# CH32V467VET-R0.net
KiCad netlist of a schematic drawn in Altium Designer
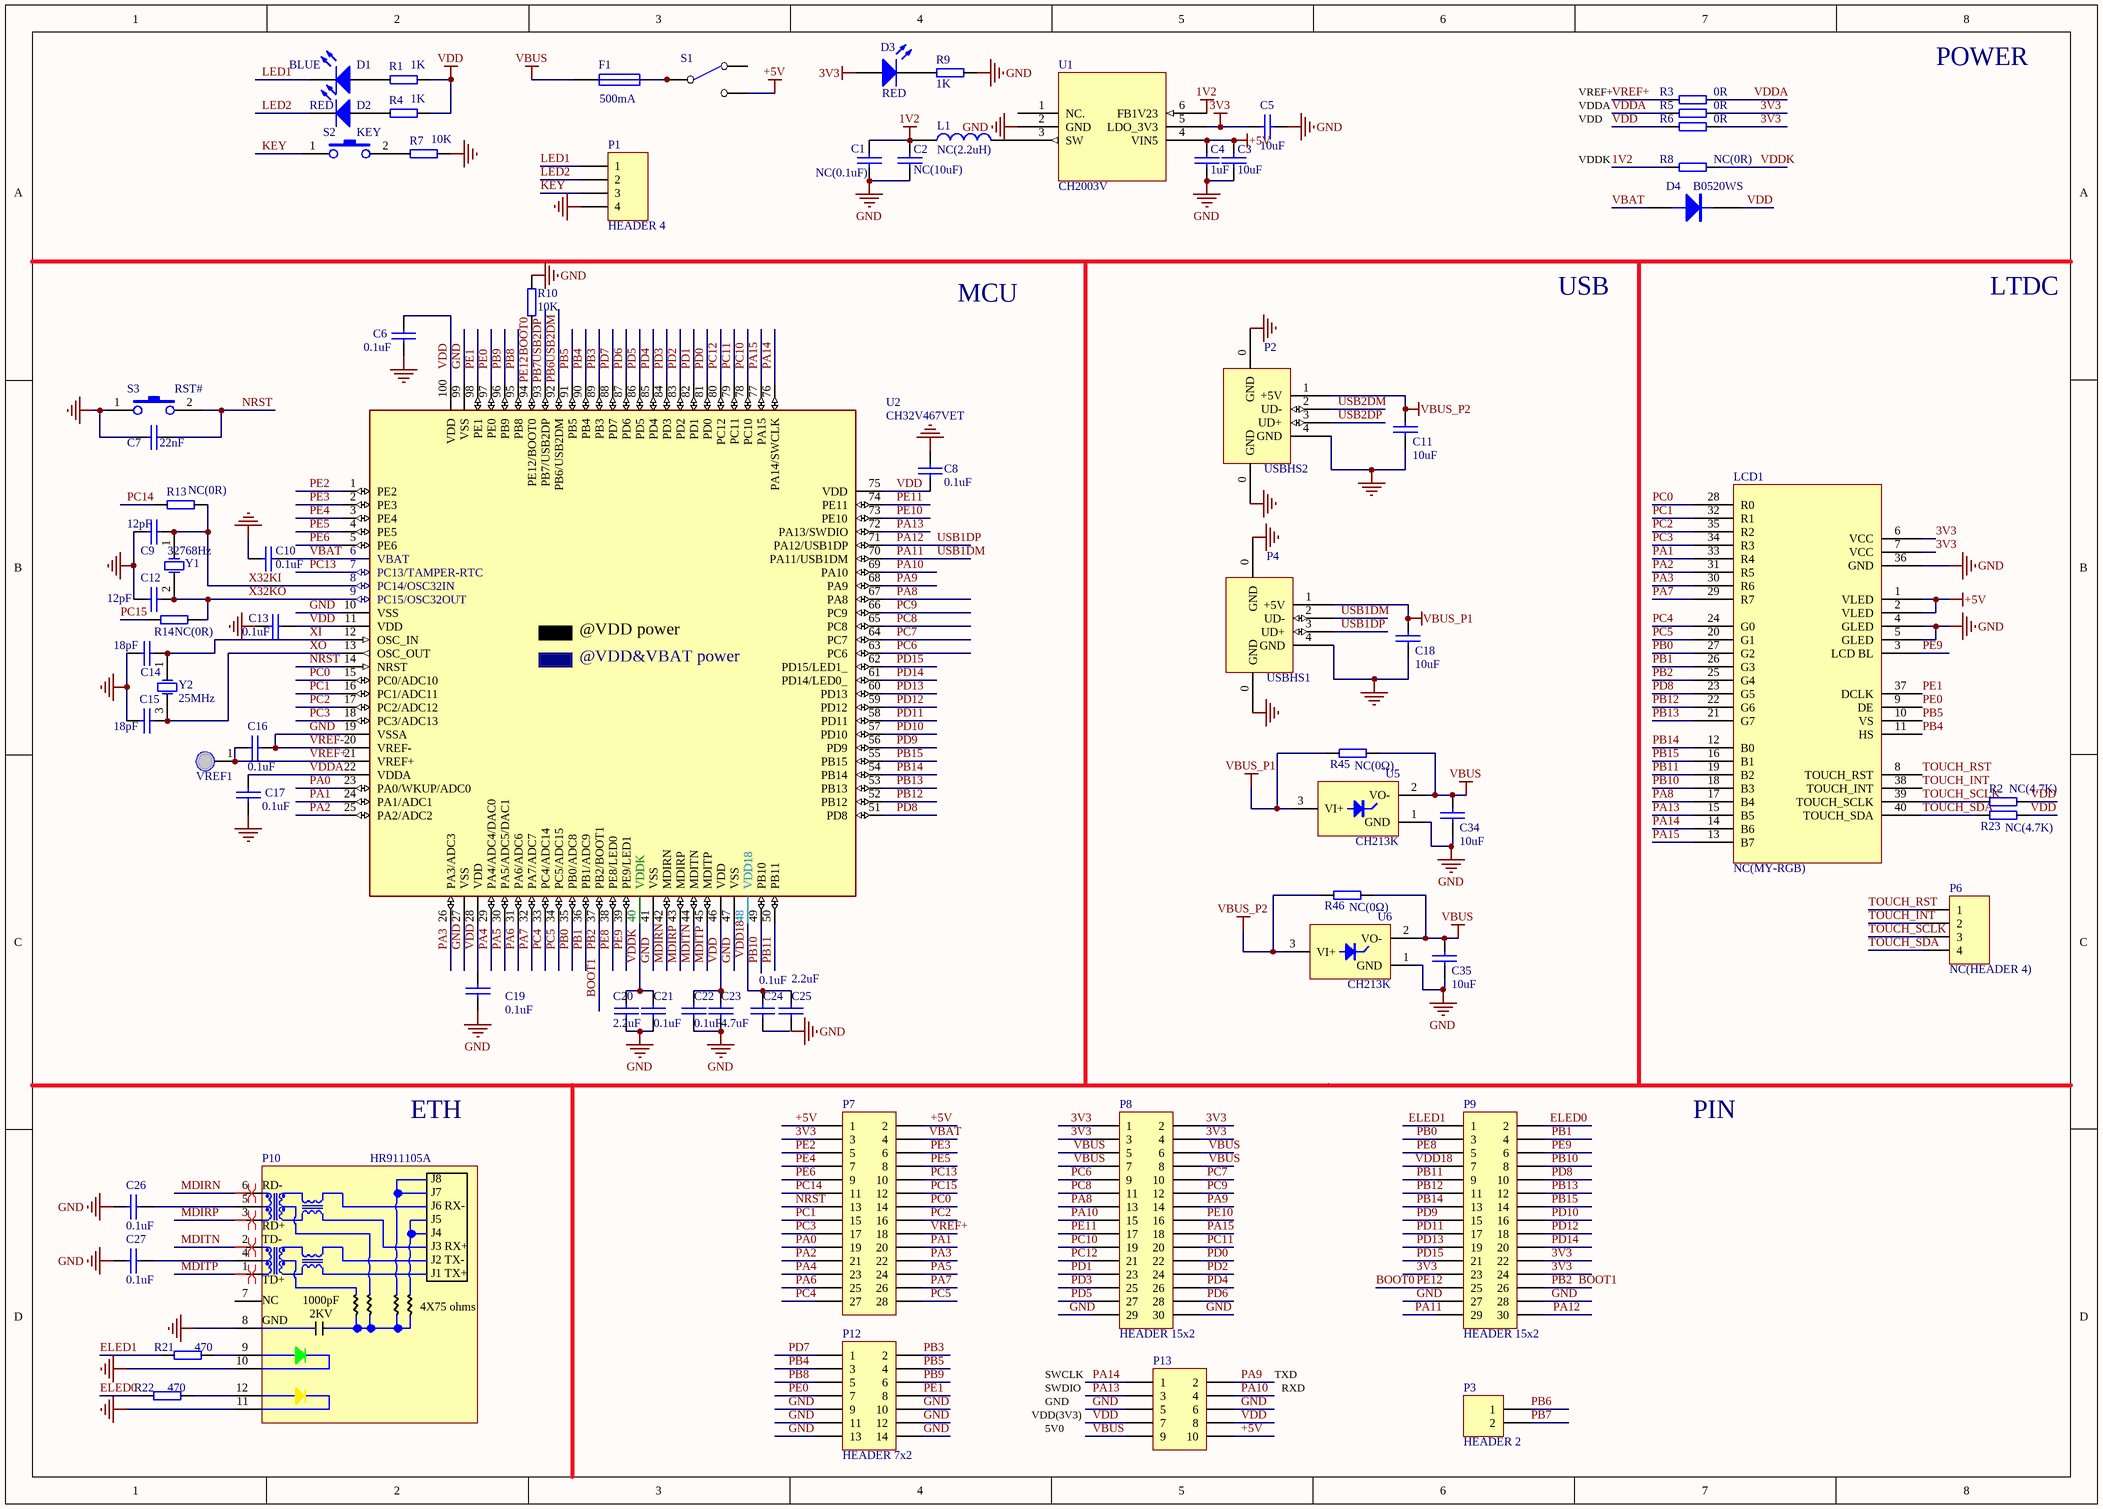
[diagram p0: CH32V467VET-R0.SchDoc]

(export (version "E")
  (design (tool "Eeschema 10.0.6"))
  (components
    (comp (ref "C1")
      (value "NC(0.1uF)")
      (footprint "0402_C")
      (description "Capacitor")
      (libsource (lib "") (part "CAP_2"))
    )
    (comp (ref "C2")
      (value "NC(10uF)")
      (footprint "0603_C")
      (description "Capacitor")
      (libsource (lib "*") (part "CAP"))
    )
    (comp (ref "C3")
      (value "10uF")
      (footprint "0603_C")
      (description "Capacitor")
      (libsource (lib "*") (part "CAP"))
    )
    (comp (ref "C4")
      (value "1uF")
      (footprint "0402_C")
      (description "Capacitor")
      (libsource (lib "") (part "CAP_2"))
    )
    (comp (ref "C5")
      (value "10uF")
      (footprint "0603_C")
      (description "Capacitor")
      (libsource (lib "*") (part "CAP"))
    )
    (comp (ref "C6")
      (value "0.1uF")
      (footprint "0402_C")
      (description "Capacitor")
      (libsource (lib "*") (part "CAP"))
    )
    (comp (ref "C7")
      (value "22nF")
      (footprint "0402_C")
      (description "Capacitor")
      (libsource (lib "") (part "CAP_1"))
    )
    (comp (ref "C8")
      (value "0.1uF")
      (footprint "0402_C")
      (description "Capacitor")
      (libsource (lib "*") (part "CAP"))
    )
    (comp (ref "C9")
      (value "12pF")
      (footprint "0402_C")
      (description "Capacitor")
      (libsource (lib "*") (part "CAP"))
    )
    (comp (ref "C10")
      (value "0.1uF")
      (footprint "0402_C")
      (description "Capacitor")
      (libsource (lib "*") (part "CAP"))
    )
    (comp (ref "C11")
      (value "10uF")
      (footprint "0603_C")
      (description "Capacitor")
      (libsource (lib "") (part "CAP_1"))
    )
    (comp (ref "C12")
      (value "12pF")
      (footprint "0402_C")
      (description "Capacitor")
      (libsource (lib "*") (part "CAP"))
    )
    (comp (ref "C13")
      (value "0.1uF")
      (footprint "0402_C")
      (description "Capacitor")
      (libsource (lib "*") (part "CAP"))
    )
    (comp (ref "C14")
      (value "18pF")
      (footprint "0402_C")
      (description "Capacitor")
      (libsource (lib "*") (part "CAP"))
    )
    (comp (ref "C15")
      (value "18pF")
      (footprint "0402_C")
      (description "Capacitor")
      (libsource (lib "*") (part "CAP"))
    )
    (comp (ref "C16")
      (value "0.1uF")
      (footprint "0402_C")
      (description "Capacitor")
      (libsource (lib "*") (part "CAP"))
    )
    (comp (ref "C17")
      (value "0.1uF")
      (footprint "0402_C")
      (description "Capacitor")
      (libsource (lib "*") (part "CAP"))
    )
    (comp (ref "C18")
      (value "10uF")
      (footprint "0603_C")
      (description "Capacitor")
      (libsource (lib "") (part "CAP_1"))
    )
    (comp (ref "C19")
      (value "0.1uF")
      (footprint "0402_C")
      (description "Capacitor")
      (libsource (lib "*") (part "CAP"))
    )
    (comp (ref "C20")
      (value "2.2uF")
      (footprint "0402_C")
      (description "Capacitor")
      (libsource (lib "*") (part "CAP"))
    )
    (comp (ref "C21")
      (value "0.1uF")
      (footprint "0402_C")
      (description "Capacitor")
      (libsource (lib "*") (part "CAP"))
    )
    (comp (ref "C22")
      (value "0.1uF")
      (footprint "0402_C")
      (description "Capacitor")
      (libsource (lib "*") (part "CAP"))
    )
    (comp (ref "C23")
      (value "4.7uF")
      (footprint "0402_C")
      (description "Capacitor")
      (libsource (lib "*") (part "CAP"))
    )
    (comp (ref "C24")
      (value "0.1uF")
      (footprint "0402_C")
      (description "Capacitor")
      (libsource (lib "*") (part "CAP"))
    )
    (comp (ref "C25")
      (value "2.2uF")
      (footprint "0402_C")
      (description "Capacitor")
      (libsource (lib "*") (part "CAP"))
    )
    (comp (ref "C26")
      (value "0.1uF")
      (footprint "0402_C")
      (description "Capacitor")
      (libsource (lib "wch_sch_others") (part "CAP"))
    )
    (comp (ref "C27")
      (value "0.1uF")
      (footprint "0402_C")
      (description "Capacitor")
      (libsource (lib "wch_sch_others") (part "CAP"))
    )
    (comp (ref "C34")
      (value "10uF")
      (footprint "0603_C")
      (description "Capacitor")
      (libsource (lib "") (part "CAP_1"))
    )
    (comp (ref "C35")
      (value "10uF")
      (footprint "0603_C")
      (description "Capacitor")
      (libsource (lib "") (part "CAP_1"))
    )
    (comp (ref "D1")
      (value "BLUE")
      (footprint "0603+")
      (description "Typical INFRARED GaAs LED")
      (fields (field (name "PUBLISHER") "Altium Limited"))
      (libsource (lib "*") (part "LED0"))
    )
    (comp (ref "D2")
      (value "RED")
      (footprint "0603+")
      (description "Typical INFRARED GaAs LED")
      (fields (field (name "PUBLISHER") "Altium Limited"))
      (libsource (lib "*") (part "LED0"))
    )
    (comp (ref "D3")
      (value "RED")
      (footprint "0603+")
      (description "Typical INFRARED GaAs LED")
      (fields (field (name "PUBLISHER") "Altium Limited"))
      (libsource (lib "*") (part "LED0"))
    )
    (comp (ref "D4")
      (value "B0520WS")
      (footprint "SOD-323")
      (description "Diode")
      (libsource (lib "*") (part "DIODE"))
    )
    (comp (ref "F1")
      (value "500mA")
      (footprint "0603")
      (description "Fuse")
      (libsource (lib "wch_sch_others") (part "FUSE1"))
    )
    (comp (ref "L1") (value "NC(2.2uH)") (footprint "CD32") (libsource (lib "*") (part "INDUCTOR")))
    (comp (ref "LCD1")
      (value "NC(MY-RGB)")
      (footprint "FPC40P-0.5-FK750M3")
      (libsource (lib "MY-显示") (part "MY-RGB"))
    )
    (comp (ref "P1")
      (value "HEADER 4")
      (footprint "SIP4-2.54mm")
      (description "Header, 4-Pin")
      (libsource (lib "wch_sch_others") (part "HEADER 4"))
    )
    (comp (ref "P2")
      (value "USBHS2")
      (footprint "USBAF")
      (description "USB Port")
      (libsource (lib "*") (part "USB"))
    )
    (comp (ref "P3")
      (value "HEADER 2")
      (footprint "MYPCB:SIP2-2.54mm")
      (description "Header, 2-Pin")
      (libsource (lib "wch_sch_others") (part "HEADER 2"))
    )
    (comp (ref "P4")
      (value "USBHS1")
      (footprint "USBAF")
      (description "USB Port")
      (libsource (lib "*") (part "USB"))
    )
    (comp (ref "P6")
      (value "NC(HEADER 4)")
      (footprint "SIP4-2.54mm")
      (description "Header, 4-Pin")
      (libsource (lib "wch_sch_others") (part "HEADER 4"))
    )
    (comp (ref "P7")
      (value "HEADER 14x2")
      (footprint "MYPCB:IDC28-2.54MM")
      (description "Header, 14-Pin, Dual row")
      (libsource (lib "wch_sch_others") (part "HEADER 14x2"))
    )
    (comp (ref "P8")
      (value "HEADER 15x2")
      (footprint "MYPCB:IDC30-2.54MM")
      (description "Header, 15-Pin, Dual row")
      (libsource (lib "wch_sch_others") (part "HEADER 15x2"))
    )
    (comp (ref "P9")
      (value "HEADER 15x2")
      (footprint "MYPCB:IDC30-2.54MM")
      (description "Header, 15-Pin, Dual row")
      (libsource (lib "wch_sch_others") (part "HEADER 15x2"))
    )
    (comp (ref "P10") (value "HR911105A") (footprint "HR911105A") (libsource (lib "*") (part "HR911105A")))
    (comp (ref "P12")
      (value "HEADER 7x2")
      (footprint "MYPCB:IDC14-2.54mm")
      (description "Header, 7-Pin, Dual row")
      (libsource (lib "wch_sch_others") (part "HEADER 7x2"))
    )
    (comp (ref "P13")
      (value "LINK")
      (footprint "IDC10-2.54mm")
      (description "Header, 5-Pin, Dual row, Right Angle")
      (fields (field (name "PUBLISHER") "Altium Limited"))
      (libsource (lib "Miscellaneous Connectors") (part "Header 5X2H"))
    )
    (comp (ref "R1") (value "1K") (footprint "0402") (libsource (lib "wch_sch_others") (part "RES")))
    (comp (ref "R2") (value "NC(4.7K)") (footprint "0402") (libsource (lib "wch_sch_others") (part "RES")))
    (comp (ref "R3") (value "0R") (footprint "0402") (libsource (lib "*") (part "R")))
    (comp (ref "R4") (value "1K") (footprint "0402") (libsource (lib "wch_sch_others") (part "RES")))
    (comp (ref "R5") (value "0R") (footprint "0402") (libsource (lib "*") (part "R")))
    (comp (ref "R6") (value "0R") (footprint "0402") (libsource (lib "*") (part "R")))
    (comp (ref "R7") (value "10K") (footprint "0402") (libsource (lib "wch_sch_others") (part "RES")))
    (comp (ref "R8") (value "NC(0R)") (footprint "0402") (libsource (lib "*") (part "R")))
    (comp (ref "R9") (value "1K") (footprint "0402") (libsource (lib "wch_sch_others") (part "RES")))
    (comp (ref "R10") (value "10K") (footprint "0402") (libsource (lib "wch_sch_others") (part "RES")))
    (comp (ref "R13") (value "NC(0R)") (footprint "0402") (libsource (lib "wch_sch_others") (part "RES")))
    (comp (ref "R14") (value "NC(0R)") (footprint "0402") (libsource (lib "wch_sch_others") (part "RES")))
    (comp (ref "R21") (value "470") (footprint "0402") (libsource (lib "wch_sch_others") (part "RES")))
    (comp (ref "R22") (value "470") (footprint "0402") (libsource (lib "wch_sch_others") (part "RES")))
    (comp (ref "R23") (value "NC(4.7K)") (footprint "0402") (libsource (lib "wch_sch_others") (part "RES")))
    (comp (ref "R45") (value "NC(0Ω)") (footprint "0402") (libsource (lib "wch_sch_others") (part "RES")))
    (comp (ref "R46") (value "NC(0Ω)") (footprint "0402") (libsource (lib "wch_sch_others") (part "RES")))
    (comp (ref "S1") (value "SW SPDT") (footprint "SW1") (libsource (lib "*") (part "SW SPDT")))
    (comp (ref "S2")
      (value "KEY")
      (footprint "SMD_6.1x3.65x2.5mm-KEY")
      (libsource (lib "wch_sch_others") (part "KEY1"))
    )
    (comp (ref "S3")
      (value "RST#")
      (footprint "SMD_6.1x3.65x2.5mm-KEY")
      (libsource (lib "wch_sch_others") (part "KEY1"))
    )
    (comp (ref "U1")
      (value "CH2003V")
      (footprint "SOT-23-6")
      (description "Step-Down DC-DC Converter, 5V input, 1.23V * 800mA output, with LDO 3.3V * 200mA")
      (libsource (lib "CHXXX") (part "CH2003V"))
    )
    (comp (ref "U2")
      (value "CH32V467VET")
      (footprint "LQFP100")
      (description "RISC-V FPU HD-MCU, 175MHz, USB_480M, 100M Ethernet & Phy, CAN, DVP, ADC, DAC, SRAM")
      (libsource (lib "CHXXX") (part "CH32V467VET"))
    )
    (comp (ref "U5")
      (value "CH213K")
      (footprint "SOT-23-3")
      (description "Ideal Diode 5V*1A")
      (libsource (lib "*") (part "CH213K"))
    )
    (comp (ref "U6")
      (value "CH213K")
      (footprint "SOT-23-3")
      (description "Ideal Diode 5V*1A")
      (libsource (lib "*") (part "CH213K"))
    )
    (comp (ref "VREF1")
      (value "PAD")
      (footprint "TESTPOINT1")
      (description "焊盘")
      (libsource (lib "wch_sch_others") (part "PAD"))
    )
    (comp (ref "Y1")
      (value "32768Hz")
      (footprint "FC-135")
      (description "Crystal Oscillator")
      (fields (field (name "PUBLISHER") "Altium Limited"))
      (libsource (lib "*") (part "XTAL"))
    )
    (comp (ref "Y2")
      (value "25MHz")
      (footprint "XT3225")
      (description "Crystal Oscillator")
      (fields (field (name "PUBLISHER") "Altium Limited"))
      (libsource (lib "") (part "XTAL_1"))
    )
  )
  (nets
    (net (code "1") (name "+5V") (class "Default")
      (node (ref "C3") (pin "2") (pinfunction "2_2") (pintype "passive"))
      (node (ref "C4") (pin "2") (pinfunction "2_2") (pintype "passive"))
      (node (ref "LCD1") (pin "1") (pinfunction "VLED_1") (pintype "passive"))
      (node (ref "LCD1") (pin "2") (pinfunction "VLED_2") (pintype "passive"))
      (node (ref "P13") (pin "10") (pinfunction "10_10") (pintype "passive"))
      (node (ref "P7") (pin "1") (pinfunction "1_1") (pintype "passive"))
      (node (ref "P7") (pin "2") (pinfunction "2_2") (pintype "passive"))
      (node (ref "S1") (pin "2") (pinfunction "NC_2") (pintype "passive"))
      (node (ref "U1") (pin "4") (pinfunction "VIN5_4") (pintype "power_in"))
    )
    (net (code "3") (name "/BOOT0") (class "Default")
      (node (ref "P9") (pin "25") (pinfunction "25_25") (pintype "passive"))
      (node (ref "R10") (pin "2") (pintype "passive"))
      (node (ref "U2") (pin "94") (pinfunction "PE12/BOOT0_94") (pintype "bidirectional"))
    )
    (net (code "4") (name "/BOOT1") (class "Default")
      (node (ref "LCD1") (pin "25") (pinfunction "G4_25") (pintype "passive"))
      (node (ref "P9") (pin "26") (pinfunction "26_26") (pintype "passive"))
      (node (ref "U2") (pin "37") (pinfunction "PB2/BOOT1_37") (pintype "bidirectional"))
    )
    (net (code "5") (name "/ELED0") (class "Default")
      (node (ref "P9") (pin "2") (pinfunction "2_2") (pintype "passive"))
      (node (ref "R22") (pin "1") (pintype "passive"))
    )
    (net (code "6") (name "/ELED1") (class "Default")
      (node (ref "P9") (pin "1") (pinfunction "1_1") (pintype "passive"))
      (node (ref "R21") (pin "1") (pintype "passive"))
    )
    (net (code "7") (name "/KEY") (class "Default")
      (node (ref "P1") (pin "3") (pinfunction "3_3") (pintype "passive"))
      (node (ref "S2") (pin "1") (pinfunction "1_1") (pintype "passive"))
    )
    (net (code "8") (name "/LED1") (class "Default")
      (node (ref "D1") (pin "2") (pinfunction "K_2") (pintype "passive"))
      (node (ref "P1") (pin "1") (pinfunction "1_1") (pintype "passive"))
    )
    (net (code "9") (name "/LED2") (class "Default")
      (node (ref "D2") (pin "2") (pinfunction "K_2") (pintype "passive"))
      (node (ref "P1") (pin "2") (pinfunction "2_2") (pintype "passive"))
    )
    (net (code "10") (name "/MDIRN") (class "Default")
      (node (ref "P10") (pin "6") (pintype "passive"))
      (node (ref "U2") (pin "42") (pinfunction "MDIRN_42") (pintype "bidirectional"))
    )
    (net (code "11") (name "/MDIRP") (class "Default")
      (node (ref "P10") (pin "3") (pintype "passive"))
      (node (ref "U2") (pin "43") (pinfunction "MDIRP_43") (pintype "bidirectional"))
    )
    (net (code "12") (name "/MDITN") (class "Default")
      (node (ref "P10") (pin "2") (pintype "passive"))
      (node (ref "U2") (pin "44") (pinfunction "MDITN_44") (pintype "bidirectional"))
    )
    (net (code "13") (name "/MDITP") (class "Default")
      (node (ref "P10") (pin "1") (pintype "passive"))
      (node (ref "U2") (pin "45") (pinfunction "MDITP_45") (pintype "bidirectional"))
    )
    (net (code "14") (name "/NRST") (class "Default")
      (node (ref "C7") (pin "2") (pinfunction "2_2") (pintype "passive"))
      (node (ref "P7") (pin "13") (pinfunction "13_13") (pintype "passive"))
      (node (ref "S3") (pin "2") (pinfunction "2_2") (pintype "passive"))
      (node (ref "U2") (pin "14") (pinfunction "NRST_14") (pintype "input"))
    )
    (net (code "15") (name "/PA0") (class "Default")
      (node (ref "P7") (pin "19") (pinfunction "19_19") (pintype "passive"))
      (node (ref "U2") (pin "23") (pinfunction "PA0/WKUP/ADC0_23") (pintype "bidirectional"))
    )
    (net (code "16") (name "/PA1") (class "Default")
      (node (ref "LCD1") (pin "33") (pinfunction "R4_33") (pintype "passive"))
      (node (ref "P7") (pin "20") (pinfunction "20_20") (pintype "passive"))
      (node (ref "U2") (pin "24") (pinfunction "PA1/ADC1_24") (pintype "bidirectional"))
    )
    (net (code "17") (name "/PA2") (class "Default")
      (node (ref "LCD1") (pin "31") (pinfunction "R5_31") (pintype "passive"))
      (node (ref "P7") (pin "21") (pinfunction "21_21") (pintype "passive"))
      (node (ref "U2") (pin "25") (pinfunction "PA2/ADC2_25") (pintype "bidirectional"))
    )
    (net (code "18") (name "/PA3") (class "Default")
      (node (ref "LCD1") (pin "30") (pinfunction "R6_30") (pintype "passive"))
      (node (ref "P7") (pin "22") (pinfunction "22_22") (pintype "passive"))
      (node (ref "U2") (pin "26") (pinfunction "PA3/ADC3_26") (pintype "bidirectional"))
    )
    (net (code "19") (name "/PA4") (class "Default")
      (node (ref "P7") (pin "23") (pinfunction "23_23") (pintype "passive"))
      (node (ref "U2") (pin "29") (pinfunction "PA4/ADC4/DAC0_29") (pintype "bidirectional"))
    )
    (net (code "20") (name "/PA5") (class "Default")
      (node (ref "P7") (pin "24") (pinfunction "24_24") (pintype "passive"))
      (node (ref "U2") (pin "30") (pinfunction "PA5/ADC5/DAC1_30") (pintype "bidirectional"))
    )
    (net (code "21") (name "/PA6") (class "Default")
      (node (ref "P7") (pin "25") (pinfunction "25_25") (pintype "passive"))
      (node (ref "U2") (pin "31") (pinfunction "PA6/ADC6_31") (pintype "bidirectional"))
    )
    (net (code "22") (name "/PA7") (class "Default")
      (node (ref "LCD1") (pin "29") (pinfunction "R7_29") (pintype "passive"))
      (node (ref "P7") (pin "26") (pinfunction "26_26") (pintype "passive"))
      (node (ref "U2") (pin "32") (pinfunction "PA7/ADC7_32") (pintype "bidirectional"))
    )
    (net (code "23") (name "/PA8") (class "Default")
      (node (ref "LCD1") (pin "17") (pinfunction "B4_17") (pintype "passive"))
      (node (ref "P8") (pin "13") (pinfunction "13_13") (pintype "passive"))
      (node (ref "U2") (pin "67") (pinfunction "PA8_67") (pintype "bidirectional"))
    )
    (net (code "24") (name "/PA9") (class "Default")
      (node (ref "P13") (pin "2") (pinfunction "2_2") (pintype "passive"))
      (node (ref "P8") (pin "14") (pinfunction "14_14") (pintype "passive"))
      (node (ref "U2") (pin "68") (pinfunction "PA9_68") (pintype "bidirectional"))
    )
    (net (code "25") (name "/PA10") (class "Default")
      (node (ref "P13") (pin "4") (pinfunction "4_4") (pintype "passive"))
      (node (ref "P8") (pin "15") (pinfunction "15_15") (pintype "passive"))
      (node (ref "U2") (pin "69") (pinfunction "PA10_69") (pintype "bidirectional"))
    )
    (net (code "26") (name "/PA11") (class "Default")
      (node (ref "P4") (pin "2") (pinfunction "UD-_2") (pintype "bidirectional"))
      (node (ref "P9") (pin "29") (pinfunction "29_29") (pintype "passive"))
      (node (ref "U2") (pin "70") (pinfunction "PA11/USB1DM_70") (pintype "bidirectional"))
    )
    (net (code "27") (name "/PA12") (class "Default")
      (node (ref "P4") (pin "3") (pinfunction "UD+_3") (pintype "bidirectional"))
      (node (ref "P9") (pin "30") (pinfunction "30_30") (pintype "passive"))
      (node (ref "U2") (pin "71") (pinfunction "PA12/USB1DP_71") (pintype "bidirectional"))
    )
    (net (code "28") (name "/PA13") (class "Default")
      (node (ref "LCD1") (pin "15") (pinfunction "B5_15") (pintype "passive"))
      (node (ref "P13") (pin "3") (pinfunction "3_3") (pintype "passive"))
      (node (ref "U2") (pin "72") (pinfunction "PA13/SWDIO_72") (pintype "bidirectional"))
    )
    (net (code "29") (name "/PA14") (class "Default")
      (node (ref "LCD1") (pin "14") (pinfunction "B6_14") (pintype "passive"))
      (node (ref "P13") (pin "1") (pinfunction "1_1") (pintype "passive"))
      (node (ref "U2") (pin "76") (pinfunction "PA14/SWCLK_76") (pintype "bidirectional"))
    )
    (net (code "30") (name "/PA15") (class "Default")
      (node (ref "LCD1") (pin "13") (pinfunction "B7_13") (pintype "passive"))
      (node (ref "P8") (pin "18") (pinfunction "18_18") (pintype "passive"))
      (node (ref "U2") (pin "77") (pinfunction "PA15_77") (pintype "bidirectional"))
    )
    (net (code "31") (name "/PB0") (class "Default")
      (node (ref "LCD1") (pin "27") (pinfunction "G2_27") (pintype "passive"))
      (node (ref "P9") (pin "3") (pinfunction "3_3") (pintype "passive"))
      (node (ref "U2") (pin "35") (pinfunction "PB0/ADC8_35") (pintype "bidirectional"))
    )
    (net (code "32") (name "/PB1") (class "Default")
      (node (ref "LCD1") (pin "26") (pinfunction "G3_26") (pintype "passive"))
      (node (ref "P9") (pin "4") (pinfunction "4_4") (pintype "passive"))
      (node (ref "U2") (pin "36") (pinfunction "PB1/ADC9_36") (pintype "bidirectional"))
    )
    (net (code "33") (name "/PB3") (class "Default")
      (node (ref "P12") (pin "2") (pinfunction "2_2") (pintype "passive"))
      (node (ref "U2") (pin "89") (pinfunction "PB3_89") (pintype "bidirectional"))
    )
    (net (code "34") (name "/PB4") (class "Default")
      (node (ref "LCD1") (pin "11") (pinfunction "HS_11") (pintype "passive"))
      (node (ref "P12") (pin "3") (pinfunction "3_3") (pintype "passive"))
      (node (ref "U2") (pin "90") (pinfunction "PB4_90") (pintype "bidirectional"))
    )
    (net (code "35") (name "/PB5") (class "Default")
      (node (ref "LCD1") (pin "10") (pinfunction "VS_10") (pintype "passive"))
      (node (ref "P12") (pin "4") (pinfunction "4_4") (pintype "passive"))
      (node (ref "U2") (pin "91") (pinfunction "PB5_91") (pintype "bidirectional"))
    )
    (net (code "36") (name "/PB6") (class "Default")
      (node (ref "P2") (pin "2") (pinfunction "UD-_2") (pintype "bidirectional"))
      (node (ref "P3") (pin "1") (pinfunction "1_1") (pintype "passive"))
      (node (ref "U2") (pin "92") (pinfunction "PB6/USB2DM_92") (pintype "bidirectional"))
    )
    (net (code "37") (name "/PB7") (class "Default")
      (node (ref "P2") (pin "3") (pinfunction "UD+_3") (pintype "bidirectional"))
      (node (ref "P3") (pin "2") (pinfunction "2_2") (pintype "passive"))
      (node (ref "U2") (pin "93") (pinfunction "PB7/USB2DP_93") (pintype "bidirectional"))
    )
    (net (code "38") (name "/PB8") (class "Default")
      (node (ref "P12") (pin "5") (pinfunction "5_5") (pintype "passive"))
      (node (ref "U2") (pin "95") (pinfunction "PB8_95") (pintype "bidirectional"))
    )
    (net (code "39") (name "/PB9") (class "Default")
      (node (ref "P12") (pin "6") (pinfunction "6_6") (pintype "passive"))
      (node (ref "U2") (pin "96") (pinfunction "PB9_96") (pintype "bidirectional"))
    )
    (net (code "40") (name "/PB10") (class "Default")
      (node (ref "LCD1") (pin "18") (pinfunction "B3_18") (pintype "passive"))
      (node (ref "P9") (pin "8") (pinfunction "8_8") (pintype "passive"))
      (node (ref "U2") (pin "49") (pinfunction "PB10_49") (pintype "bidirectional"))
    )
    (net (code "41") (name "/PB11") (class "Default")
      (node (ref "LCD1") (pin "19") (pinfunction "B2_19") (pintype "passive"))
      (node (ref "P9") (pin "9") (pinfunction "9_9") (pintype "passive"))
      (node (ref "U2") (pin "50") (pinfunction "PB11_50") (pintype "bidirectional"))
    )
    (net (code "42") (name "/PB12") (class "Default")
      (node (ref "LCD1") (pin "22") (pinfunction "G6_22") (pintype "passive"))
      (node (ref "P9") (pin "11") (pinfunction "11_11") (pintype "passive"))
      (node (ref "U2") (pin "52") (pinfunction "PB12_52") (pintype "bidirectional"))
    )
    (net (code "43") (name "/PB13") (class "Default")
      (node (ref "LCD1") (pin "21") (pinfunction "G7_21") (pintype "passive"))
      (node (ref "P9") (pin "12") (pinfunction "12_12") (pintype "passive"))
      (node (ref "U2") (pin "53") (pinfunction "PB13_53") (pintype "bidirectional"))
    )
    (net (code "44") (name "/PB14") (class "Default")
      (node (ref "LCD1") (pin "12") (pinfunction "B0_12") (pintype "passive"))
      (node (ref "P9") (pin "13") (pinfunction "13_13") (pintype "passive"))
      (node (ref "U2") (pin "54") (pinfunction "PB14_54") (pintype "bidirectional"))
    )
    (net (code "45") (name "/PB15") (class "Default")
      (node (ref "LCD1") (pin "16") (pinfunction "B1_16") (pintype "passive"))
      (node (ref "P9") (pin "14") (pinfunction "14_14") (pintype "passive"))
      (node (ref "U2") (pin "55") (pinfunction "PB15_55") (pintype "bidirectional"))
    )
    (net (code "46") (name "/PC0") (class "Default")
      (node (ref "LCD1") (pin "28") (pinfunction "R0_28") (pintype "passive"))
      (node (ref "P7") (pin "14") (pinfunction "14_14") (pintype "passive"))
      (node (ref "U2") (pin "15") (pinfunction "PC0/ADC10_15") (pintype "bidirectional"))
    )
    (net (code "47") (name "/PC1") (class "Default")
      (node (ref "LCD1") (pin "32") (pinfunction "R1_32") (pintype "passive"))
      (node (ref "P7") (pin "15") (pinfunction "15_15") (pintype "passive"))
      (node (ref "U2") (pin "16") (pinfunction "PC1/ADC11_16") (pintype "bidirectional"))
    )
    (net (code "48") (name "/PC2") (class "Default")
      (node (ref "LCD1") (pin "35") (pinfunction "R2_35") (pintype "passive"))
      (node (ref "P7") (pin "16") (pinfunction "16_16") (pintype "passive"))
      (node (ref "U2") (pin "17") (pinfunction "PC2/ADC12_17") (pintype "bidirectional"))
    )
    (net (code "49") (name "/PC3") (class "Default")
      (node (ref "LCD1") (pin "34") (pinfunction "R3_34") (pintype "passive"))
      (node (ref "P7") (pin "17") (pinfunction "17_17") (pintype "passive"))
      (node (ref "U2") (pin "18") (pinfunction "PC3/ADC13_18") (pintype "bidirectional"))
    )
    (net (code "50") (name "/PC4") (class "Default")
      (node (ref "LCD1") (pin "24") (pinfunction "G0_24") (pintype "passive"))
      (node (ref "P7") (pin "27") (pinfunction "27_27") (pintype "passive"))
      (node (ref "U2") (pin "33") (pinfunction "PC4/ADC14_33") (pintype "bidirectional"))
    )
    (net (code "51") (name "/PC5") (class "Default")
      (node (ref "LCD1") (pin "20") (pinfunction "G1_20") (pintype "passive"))
      (node (ref "P7") (pin "28") (pinfunction "28_28") (pintype "passive"))
      (node (ref "U2") (pin "34") (pinfunction "PC5/ADC15_34") (pintype "bidirectional"))
    )
    (net (code "52") (name "/PC6") (class "Default")
      (node (ref "P8") (pin "9") (pinfunction "9_9") (pintype "passive"))
      (node (ref "U2") (pin "63") (pinfunction "PC6_63") (pintype "bidirectional"))
    )
    (net (code "53") (name "/PC7") (class "Default")
      (node (ref "P8") (pin "10") (pinfunction "10_10") (pintype "passive"))
      (node (ref "U2") (pin "64") (pinfunction "PC7_64") (pintype "bidirectional"))
    )
    (net (code "54") (name "/PC8") (class "Default")
      (node (ref "P8") (pin "11") (pinfunction "11_11") (pintype "passive"))
      (node (ref "U2") (pin "65") (pinfunction "PC8_65") (pintype "bidirectional"))
    )
    (net (code "55") (name "/PC9") (class "Default")
      (node (ref "P8") (pin "12") (pinfunction "12_12") (pintype "passive"))
      (node (ref "U2") (pin "66") (pinfunction "PC9_66") (pintype "bidirectional"))
    )
    (net (code "56") (name "/PC10") (class "Default")
      (node (ref "P8") (pin "19") (pinfunction "19_19") (pintype "passive"))
      (node (ref "U2") (pin "78") (pinfunction "PC10_78") (pintype "bidirectional"))
    )
    (net (code "57") (name "/PC11") (class "Default")
      (node (ref "P8") (pin "20") (pinfunction "20_20") (pintype "passive"))
      (node (ref "U2") (pin "79") (pinfunction "PC11_79") (pintype "bidirectional"))
    )
    (net (code "58") (name "/PC12") (class "Default")
      (node (ref "P8") (pin "21") (pinfunction "21_21") (pintype "passive"))
      (node (ref "U2") (pin "80") (pinfunction "PC12_80") (pintype "bidirectional"))
    )
    (net (code "59") (name "/PC13") (class "Default")
      (node (ref "P7") (pin "10") (pinfunction "10_10") (pintype "passive"))
      (node (ref "U2") (pin "7") (pinfunction "PC13/TAMPER-RTC_7") (pintype "bidirectional"))
    )
    (net (code "60") (name "/PC14") (class "Default")
      (node (ref "P7") (pin "11") (pinfunction "11_11") (pintype "passive"))
      (node (ref "R13") (pin "1") (pintype "passive"))
    )
    (net (code "61") (name "/PC15") (class "Default")
      (node (ref "P7") (pin "12") (pinfunction "12_12") (pintype "passive"))
      (node (ref "R14") (pin "1") (pintype "passive"))
    )
    (net (code "62") (name "/PD0") (class "Default")
      (node (ref "P8") (pin "22") (pinfunction "22_22") (pintype "passive"))
      (node (ref "U2") (pin "81") (pinfunction "PD0_81") (pintype "bidirectional"))
    )
    (net (code "63") (name "/PD1") (class "Default")
      (node (ref "P8") (pin "23") (pinfunction "23_23") (pintype "passive"))
      (node (ref "U2") (pin "82") (pinfunction "PD1_82") (pintype "bidirectional"))
    )
    (net (code "64") (name "/PD2") (class "Default")
      (node (ref "P8") (pin "24") (pinfunction "24_24") (pintype "passive"))
      (node (ref "U2") (pin "83") (pinfunction "PD2_83") (pintype "bidirectional"))
    )
    (net (code "65") (name "/PD3") (class "Default")
      (node (ref "P8") (pin "25") (pinfunction "25_25") (pintype "passive"))
      (node (ref "U2") (pin "84") (pinfunction "PD3_84") (pintype "bidirectional"))
    )
    (net (code "66") (name "/PD4") (class "Default")
      (node (ref "P8") (pin "26") (pinfunction "26_26") (pintype "passive"))
      (node (ref "U2") (pin "85") (pinfunction "PD4_85") (pintype "bidirectional"))
    )
    (net (code "67") (name "/PD5") (class "Default")
      (node (ref "P8") (pin "27") (pinfunction "27_27") (pintype "passive"))
      (node (ref "U2") (pin "86") (pinfunction "PD5_86") (pintype "bidirectional"))
    )
    (net (code "68") (name "/PD6") (class "Default")
      (node (ref "P8") (pin "28") (pinfunction "28_28") (pintype "passive"))
      (node (ref "U2") (pin "87") (pinfunction "PD6_87") (pintype "bidirectional"))
    )
    (net (code "69") (name "/PD7") (class "Default")
      (node (ref "P12") (pin "1") (pinfunction "1_1") (pintype "passive"))
      (node (ref "U2") (pin "88") (pinfunction "PD7_88") (pintype "bidirectional"))
    )
    (net (code "70") (name "/PD8") (class "Default")
      (node (ref "LCD1") (pin "23") (pinfunction "G5_23") (pintype "passive"))
      (node (ref "P9") (pin "10") (pinfunction "10_10") (pintype "passive"))
      (node (ref "U2") (pin "51") (pinfunction "PD8_51") (pintype "bidirectional"))
    )
    (net (code "71") (name "/PD9") (class "Default")
      (node (ref "P9") (pin "15") (pinfunction "15_15") (pintype "passive"))
      (node (ref "U2") (pin "56") (pinfunction "PD9_56") (pintype "bidirectional"))
    )
    (net (code "72") (name "/PD10") (class "Default")
      (node (ref "P9") (pin "16") (pinfunction "16_16") (pintype "passive"))
      (node (ref "U2") (pin "57") (pinfunction "PD10_57") (pintype "bidirectional"))
    )
    (net (code "73") (name "/PD11") (class "Default")
      (node (ref "P9") (pin "17") (pinfunction "17_17") (pintype "passive"))
      (node (ref "U2") (pin "58") (pinfunction "PD11_58") (pintype "bidirectional"))
    )
    (net (code "74") (name "/PD12") (class "Default")
      (node (ref "P9") (pin "18") (pinfunction "18_18") (pintype "passive"))
      (node (ref "U2") (pin "59") (pinfunction "PD12_59") (pintype "bidirectional"))
    )
    (net (code "75") (name "/PD13") (class "Default")
      (node (ref "P9") (pin "19") (pinfunction "19_19") (pintype "passive"))
      (node (ref "U2") (pin "60") (pinfunction "PD13_60") (pintype "bidirectional"))
    )
    (net (code "76") (name "/PD14") (class "Default")
      (node (ref "P9") (pin "20") (pinfunction "20_20") (pintype "passive"))
      (node (ref "U2") (pin "61") (pinfunction "PD14/LED0__61") (pintype "bidirectional"))
    )
    (net (code "77") (name "/PD15") (class "Default")
      (node (ref "P9") (pin "21") (pinfunction "21_21") (pintype "passive"))
      (node (ref "U2") (pin "62") (pinfunction "PD15/LED1__62") (pintype "bidirectional"))
    )
    (net (code "78") (name "/PE0") (class "Default")
      (node (ref "LCD1") (pin "9") (pinfunction "DE_9") (pintype "passive"))
      (node (ref "P12") (pin "7") (pinfunction "7_7") (pintype "passive"))
      (node (ref "U2") (pin "97") (pinfunction "PE0_97") (pintype "bidirectional"))
    )
    (net (code "79") (name "/PE1") (class "Default")
      (node (ref "LCD1") (pin "37") (pinfunction "DCLK_37") (pintype "passive"))
      (node (ref "P12") (pin "8") (pinfunction "8_8") (pintype "passive"))
      (node (ref "U2") (pin "98") (pinfunction "PE1_98") (pintype "bidirectional"))
    )
    (net (code "80") (name "/PE2") (class "Default")
      (node (ref "P7") (pin "5") (pinfunction "5_5") (pintype "passive"))
      (node (ref "U2") (pin "1") (pinfunction "PE2_1") (pintype "bidirectional"))
    )
    (net (code "81") (name "/PE3") (class "Default")
      (node (ref "P7") (pin "6") (pinfunction "6_6") (pintype "passive"))
      (node (ref "U2") (pin "2") (pinfunction "PE3_2") (pintype "bidirectional"))
    )
    (net (code "82") (name "/PE4") (class "Default")
      (node (ref "P7") (pin "7") (pinfunction "7_7") (pintype "passive"))
      (node (ref "U2") (pin "3") (pinfunction "PE4_3") (pintype "bidirectional"))
    )
    (net (code "83") (name "/PE5") (class "Default")
      (node (ref "P7") (pin "8") (pinfunction "8_8") (pintype "passive"))
      (node (ref "U2") (pin "4") (pinfunction "PE5_4") (pintype "bidirectional"))
    )
    (net (code "84") (name "/PE6") (class "Default")
      (node (ref "P7") (pin "9") (pinfunction "9_9") (pintype "passive"))
      (node (ref "U2") (pin "5") (pinfunction "PE6_5") (pintype "bidirectional"))
    )
    (net (code "85") (name "/PE8") (class "Default")
      (node (ref "P9") (pin "5") (pinfunction "5_5") (pintype "passive"))
      (node (ref "U2") (pin "38") (pinfunction "PE8/LED0_38") (pintype "bidirectional"))
    )
    (net (code "86") (name "/PE9") (class "Default")
      (node (ref "LCD1") (pin "3") (pinfunction "LCD_BL_3") (pintype "passive"))
      (node (ref "P9") (pin "6") (pinfunction "6_6") (pintype "passive"))
      (node (ref "U2") (pin "39") (pinfunction "PE9/LED1_39") (pintype "bidirectional"))
    )
    (net (code "87") (name "/PE10") (class "Default")
      (node (ref "P8") (pin "16") (pinfunction "16_16") (pintype "passive"))
      (node (ref "U2") (pin "73") (pinfunction "PE10_73") (pintype "bidirectional"))
    )
    (net (code "88") (name "/PE11") (class "Default")
      (node (ref "P8") (pin "17") (pinfunction "17_17") (pintype "passive"))
      (node (ref "U2") (pin "74") (pinfunction "PE11_74") (pintype "bidirectional"))
    )
    (net (code "89") (name "/TOUCH_INT") (class "Default")
      (node (ref "LCD1") (pin "38") (pinfunction "TOUCH_INT_38") (pintype "passive"))
      (node (ref "P6") (pin "2") (pinfunction "2_2") (pintype "passive"))
    )
    (net (code "90") (name "/TOUCH_RST") (class "Default")
      (node (ref "LCD1") (pin "8") (pinfunction "TOUCH_RST_8") (pintype "passive"))
      (node (ref "P6") (pin "1") (pinfunction "1_1") (pintype "passive"))
    )
    (net (code "91") (name "/TOUCH_SCLK") (class "Default")
      (node (ref "LCD1") (pin "39") (pinfunction "TOUCH_SCLK_39") (pintype "passive"))
      (node (ref "P6") (pin "3") (pinfunction "3_3") (pintype "passive"))
      (node (ref "R2") (pin "2") (pintype "passive"))
    )
    (net (code "92") (name "/TOUCH_SDA") (class "Default")
      (node (ref "LCD1") (pin "40") (pinfunction "TOUCH_SDA_40") (pintype "passive"))
      (node (ref "P6") (pin "4") (pinfunction "4_4") (pintype "passive"))
      (node (ref "R23") (pin "2") (pintype "passive"))
    )
    (net (code "93") (name "/VBAT") (class "Default")
      (node (ref "C10") (pin "2") (pinfunction "2_2") (pintype "passive"))
      (node (ref "D4") (pin "1") (pinfunction "A_1") (pintype "passive"))
      (node (ref "P7") (pin "4") (pinfunction "4_4") (pintype "passive"))
      (node (ref "U2") (pin "6") (pinfunction "VBAT_6") (pintype "power_in"))
    )
    (net (code "94") (name "/VDD18") (class "Default")
      (node (ref "C24") (pin "2") (pinfunction "2_2") (pintype "passive"))
      (node (ref "C25") (pin "2") (pinfunction "2_2") (pintype "passive"))
      (node (ref "P9") (pin "7") (pinfunction "7_7") (pintype "passive"))
      (node (ref "U2") (pin "48") (pinfunction "VDD18_48") (pintype "power_in"))
    )
    (net (code "95") (name "/VDDA") (class "Default")
      (node (ref "C17") (pin "1") (pinfunction "1_1") (pintype "passive"))
      (node (ref "R3") (pin "1") (pinfunction "1_1") (pintype "passive"))
      (node (ref "R5") (pin "2") (pinfunction "2_2") (pintype "passive"))
      (node (ref "U2") (pin "22") (pinfunction "VDDA_22") (pintype "power_in"))
    )
    (net (code "96") (name "/VDDK") (class "Default")
      (node (ref "C20") (pin "2") (pinfunction "2_2") (pintype "passive"))
      (node (ref "C21") (pin "2") (pinfunction "2_2") (pintype "passive"))
      (node (ref "R8") (pin "1") (pinfunction "1_1") (pintype "passive"))
      (node (ref "U2") (pin "40") (pinfunction "VDDK_40") (pintype "power_in"))
    )
    (net (code "97") (name "/VREF+") (class "Default")
      (node (ref "C16") (pin "1") (pinfunction "1_1") (pintype "passive"))
      (node (ref "P7") (pin "18") (pinfunction "18_18") (pintype "passive"))
      (node (ref "R3") (pin "2") (pinfunction "2_2") (pintype "passive"))
      (node (ref "U2") (pin "21") (pinfunction "VREF+_21") (pintype "power_in"))
      (node (ref "VREF1") (pin "1") (pintype "passive"))
    )
    (net (code "98") (name "/X32KI") (class "Default")
      (node (ref "C9") (pin "2") (pinfunction "2_2") (pintype "passive"))
      (node (ref "R13") (pin "2") (pintype "passive"))
      (node (ref "U2") (pin "8") (pinfunction "PC14/OSC32IN_8") (pintype "bidirectional"))
      (node (ref "Y1") (pin "1") (pinfunction "OSC1_1") (pintype "passive"))
    )
    (net (code "99") (name "/X32KO") (class "Default")
      (node (ref "C12") (pin "2") (pinfunction "2_2") (pintype "passive"))
      (node (ref "R14") (pin "2") (pintype "passive"))
      (node (ref "U2") (pin "9") (pinfunction "PC15/OSC32OUT_9") (pintype "bidirectional"))
      (node (ref "Y1") (pin "2") (pinfunction "OSC2_2") (pintype "passive"))
    )
    (net (code "100") (name "/XI") (class "Default")
      (node (ref "C14") (pin "2") (pinfunction "2_2") (pintype "passive"))
      (node (ref "U2") (pin "12") (pinfunction "OSC_IN_12") (pintype "input"))
      (node (ref "Y2") (pin "1") (pinfunction "OSC1_1") (pintype "passive"))
    )
    (net (code "101") (name "/XO") (class "Default")
      (node (ref "C15") (pin "2") (pinfunction "2_2") (pintype "passive"))
      (node (ref "U2") (pin "13") (pinfunction "OSC_OUT_13") (pintype "output"))
      (node (ref "Y2") (pin "3") (pinfunction "OSC2_3") (pintype "passive"))
    )
    (net (code "102") (name "1V2") (class "Default")
      (node (ref "C1") (pin "2") (pinfunction "2_2") (pintype "passive"))
      (node (ref "C2") (pin "2") (pinfunction "2_2") (pintype "passive"))
      (node (ref "L1") (pin "2") (pinfunction "2_2") (pintype "passive"))
      (node (ref "R8") (pin "2") (pinfunction "2_2") (pintype "passive"))
      (node (ref "U1") (pin "6") (pinfunction "FB1V23_6") (pintype "input"))
    )
    (net (code "103") (name "3V3") (class "Default")
      (node (ref "C5") (pin "2") (pinfunction "2_2") (pintype "passive"))
      (node (ref "D3") (pin "1") (pinfunction "A_1") (pintype "passive"))
      (node (ref "LCD1") (pin "6") (pinfunction "VCC_6") (pintype "passive"))
      (node (ref "LCD1") (pin "7") (pinfunction "VCC_7") (pintype "passive"))
      (node (ref "P7") (pin "3") (pinfunction "3_3") (pintype "passive"))
      (node (ref "P8") (pin "1") (pinfunction "1_1") (pintype "passive"))
      (node (ref "P8") (pin "2") (pinfunction "2_2") (pintype "passive"))
      (node (ref "P8") (pin "3") (pinfunction "3_3") (pintype "passive"))
      (node (ref "P8") (pin "4") (pinfunction "4_4") (pintype "passive"))
      (node (ref "P9") (pin "22") (pinfunction "22_22") (pintype "passive"))
      (node (ref "P9") (pin "23") (pinfunction "23_23") (pintype "passive"))
      (node (ref "P9") (pin "24") (pinfunction "24_24") (pintype "passive"))
      (node (ref "R5") (pin "1") (pinfunction "1_1") (pintype "passive"))
      (node (ref "R6") (pin "1") (pinfunction "1_1") (pintype "passive"))
      (node (ref "U1") (pin "5") (pinfunction "LDO_3V3_5") (pintype "power_in"))
    )
    (net (code "104") (name "GND") (class "Default")
      (node (ref "C1") (pin "1") (pinfunction "1_1") (pintype "passive"))
      (node (ref "C10") (pin "1") (pinfunction "1_1") (pintype "passive"))
      (node (ref "C11") (pin "2") (pinfunction "2_2") (pintype "passive"))
      (node (ref "C12") (pin "1") (pinfunction "1_1") (pintype "passive"))
      (node (ref "C13") (pin "2") (pinfunction "2_2") (pintype "passive"))
      (node (ref "C14") (pin "1") (pinfunction "1_1") (pintype "passive"))
      (node (ref "C15") (pin "1") (pinfunction "1_1") (pintype "passive"))
      (node (ref "C16") (pin "2") (pinfunction "2_2") (pintype "passive"))
      (node (ref "C17") (pin "2") (pinfunction "2_2") (pintype "passive"))
      (node (ref "C18") (pin "2") (pinfunction "2_2") (pintype "passive"))
      (node (ref "C19") (pin "1") (pinfunction "1_1") (pintype "passive"))
      (node (ref "C2") (pin "1") (pinfunction "1_1") (pintype "passive"))
      (node (ref "C20") (pin "1") (pinfunction "1_1") (pintype "passive"))
      (node (ref "C21") (pin "1") (pinfunction "1_1") (pintype "passive"))
      (node (ref "C22") (pin "1") (pinfunction "1_1") (pintype "passive"))
      (node (ref "C23") (pin "1") (pinfunction "1_1") (pintype "passive"))
      (node (ref "C25") (pin "1") (pinfunction "1_1") (pintype "passive"))
      (node (ref "C26") (pin "1") (pinfunction "1_1") (pintype "passive"))
      (node (ref "C27") (pin "1") (pinfunction "1_1") (pintype "passive"))
      (node (ref "C3") (pin "1") (pinfunction "1_1") (pintype "passive"))
      (node (ref "C34") (pin "2") (pinfunction "2_2") (pintype "passive"))
      (node (ref "C35") (pin "2") (pinfunction "2_2") (pintype "passive"))
      (node (ref "C4") (pin "1") (pinfunction "1_1") (pintype "passive"))
      (node (ref "C5") (pin "1") (pinfunction "1_1") (pintype "passive"))
      (node (ref "C6") (pin "1") (pinfunction "1_1") (pintype "passive"))
      (node (ref "C7") (pin "1") (pinfunction "1_1") (pintype "passive"))
      (node (ref "C8") (pin "2") (pinfunction "2_2") (pintype "passive"))
      (node (ref "C9") (pin "1") (pinfunction "1_1") (pintype "passive"))
      (node (ref "LCD1") (pin "36") (pinfunction "GND_36") (pintype "passive"))
      (node (ref "LCD1") (pin "4") (pinfunction "GLED_4") (pintype "passive"))
      (node (ref "LCD1") (pin "5") (pinfunction "GLED_5") (pintype "passive"))
      (node (ref "P1") (pin "4") (pinfunction "4_4") (pintype "passive"))
      (node (ref "P10") (pin "10") (pintype "passive"))
      (node (ref "P10") (pin "11") (pintype "passive"))
      (node (ref "P10") (pin "8") (pintype "passive"))
      (node (ref "P12") (pin "10") (pinfunction "10_10") (pintype "passive"))
      (node (ref "P12") (pin "11") (pinfunction "11_11") (pintype "passive"))
      (node (ref "P12") (pin "12") (pinfunction "12_12") (pintype "passive"))
      (node (ref "P12") (pin "13") (pinfunction "13_13") (pintype "passive"))
      (node (ref "P12") (pin "14") (pinfunction "14_14") (pintype "passive"))
      (node (ref "P12") (pin "9") (pinfunction "9_9") (pintype "passive"))
      (node (ref "P13") (pin "5") (pinfunction "5_5") (pintype "passive"))
      (node (ref "P13") (pin "6") (pinfunction "6_6") (pintype "passive"))
      (node (ref "P2") (pin "0") (pinfunction "GND_0") (pintype "power_in"))
      (node (ref "P2") (pin "4") (pinfunction "GND_4") (pintype "power_in"))
      (node (ref "P4") (pin "0") (pinfunction "GND_0") (pintype "power_in"))
      (node (ref "P4") (pin "4") (pinfunction "GND_4") (pintype "power_in"))
      (node (ref "P8") (pin "29") (pinfunction "29_29") (pintype "passive"))
      (node (ref "P8") (pin "30") (pinfunction "30_30") (pintype "passive"))
      (node (ref "P9") (pin "27") (pinfunction "27_27") (pintype "passive"))
      (node (ref "P9") (pin "28") (pinfunction "28_28") (pintype "passive"))
      (node (ref "R10") (pin "1") (pintype "passive"))
      (node (ref "R7") (pin "1") (pintype "passive"))
      (node (ref "R9") (pin "2") (pintype "passive"))
      (node (ref "S3") (pin "1") (pinfunction "1_1") (pintype "passive"))
      (node (ref "U1") (pin "2") (pinfunction "GND_2") (pintype "power_in"))
      (node (ref "U2") (pin "10") (pinfunction "VSS_10") (pintype "power_in"))
      (node (ref "U2") (pin "19") (pinfunction "VSSA_19") (pintype "power_in"))
      (node (ref "U2") (pin "20") (pinfunction "VREF-_20") (pintype "power_in"))
      (node (ref "U2") (pin "27") (pinfunction "VSS_27") (pintype "power_in"))
      (node (ref "U2") (pin "41") (pinfunction "VSS_41") (pintype "power_in"))
      (node (ref "U2") (pin "47") (pinfunction "VSS_47") (pintype "power_in"))
      (node (ref "U2") (pin "99") (pinfunction "VSS_99") (pintype "power_in"))
      (node (ref "U5") (pin "1") (pinfunction "GND_1") (pintype "power_in"))
      (node (ref "U6") (pin "1") (pinfunction "GND_1") (pintype "power_in"))
    )
    (net (code "105") (name "Net-(C26-Pad2)") (class "Default")
      (node (ref "C26") (pin "2") (pinfunction "2_2") (pintype "passive"))
      (node (ref "P10") (pin "5") (pintype "passive"))
    )
    (net (code "106") (name "Net-(C27-Pad2)") (class "Default")
      (node (ref "C27") (pin "2") (pinfunction "2_2") (pintype "passive"))
      (node (ref "P10") (pin "4") (pintype "passive"))
    )
    (net (code "107") (name "Net-(D1-A)") (class "Default")
      (node (ref "D1") (pin "1") (pinfunction "A_1") (pintype "passive"))
      (node (ref "R1") (pin "2") (pintype "passive"))
    )
    (net (code "108") (name "Net-(D2-A)") (class "Default")
      (node (ref "D2") (pin "1") (pinfunction "A_1") (pintype "passive"))
      (node (ref "R4") (pin "2") (pintype "passive"))
    )
    (net (code "109") (name "Net-(D3-K)") (class "Default")
      (node (ref "D3") (pin "2") (pinfunction "K_2") (pintype "passive"))
      (node (ref "R9") (pin "1") (pintype "passive"))
    )
    (net (code "110") (name "Net-(P10-Pad9)") (class "Default")
      (node (ref "P10") (pin "9") (pintype "passive"))
      (node (ref "R21") (pin "2") (pintype "passive"))
    )
    (net (code "111") (name "Net-(P10-Pad12)") (class "Default")
      (node (ref "P10") (pin "12") (pintype "passive"))
      (node (ref "R22") (pin "2") (pintype "passive"))
    )
    (net (code "112") (name "Net-(R7-Pad2)") (class "Default")
      (node (ref "R7") (pin "2") (pintype "passive"))
      (node (ref "S2") (pin "2") (pinfunction "2_2") (pintype "passive"))
    )
    (net (code "113") (name "Net-(S1-COMMON)") (class "Default")
      (node (ref "F1") (pin "2") (pinfunction "2_2") (pintype "passive"))
      (node (ref "S1") (pin "1") (pinfunction "COMMON_1") (pintype "passive"))
    )
    (net (code "114") (name "Net-(U1-SW)") (class "Default")
      (node (ref "L1") (pin "1") (pinfunction "1_1") (pintype "passive"))
      (node (ref "U1") (pin "3") (pinfunction "SW_3") (pintype "output"))
    )
    (net (code "115") (name "VBUS") (class "Default")
      (node (ref "C34") (pin "1") (pinfunction "1_1") (pintype "passive"))
      (node (ref "C35") (pin "1") (pinfunction "1_1") (pintype "passive"))
      (node (ref "F1") (pin "1") (pinfunction "1_1") (pintype "passive"))
      (node (ref "P13") (pin "9") (pinfunction "9_9") (pintype "passive"))
      (node (ref "P8") (pin "5") (pinfunction "5_5") (pintype "passive"))
      (node (ref "P8") (pin "6") (pinfunction "6_6") (pintype "passive"))
      (node (ref "P8") (pin "7") (pinfunction "7_7") (pintype "passive"))
      (node (ref "P8") (pin "8") (pinfunction "8_8") (pintype "passive"))
      (node (ref "R45") (pin "1") (pintype "passive"))
      (node (ref "R46") (pin "1") (pintype "passive"))
      (node (ref "U5") (pin "2") (pinfunction "VO-_2") (pintype "power_in"))
      (node (ref "U6") (pin "2") (pinfunction "VO-_2") (pintype "power_in"))
    )
    (net (code "116") (name "VBUS_P1") (class "Default")
      (node (ref "C18") (pin "1") (pinfunction "1_1") (pintype "passive"))
      (node (ref "P4") (pin "1") (pinfunction "+5V_1") (pintype "power_in"))
      (node (ref "R45") (pin "2") (pintype "passive"))
      (node (ref "U5") (pin "3") (pinfunction "VI+_3") (pintype "power_in"))
    )
    (net (code "117") (name "VBUS_P2") (class "Default")
      (node (ref "C11") (pin "1") (pinfunction "1_1") (pintype "passive"))
      (node (ref "P2") (pin "1") (pinfunction "+5V_1") (pintype "power_in"))
      (node (ref "R46") (pin "2") (pintype "passive"))
      (node (ref "U6") (pin "3") (pinfunction "VI+_3") (pintype "power_in"))
    )
    (net (code "118") (name "VDD") (class "Default")
      (node (ref "C13") (pin "1") (pinfunction "1_1") (pintype "passive"))
      (node (ref "C19") (pin "2") (pinfunction "2_2") (pintype "passive"))
      (node (ref "C22") (pin "2") (pinfunction "2_2") (pintype "passive"))
      (node (ref "C23") (pin "2") (pinfunction "2_2") (pintype "passive"))
      (node (ref "C6") (pin "2") (pinfunction "2_2") (pintype "passive"))
      (node (ref "C8") (pin "1") (pinfunction "1_1") (pintype "passive"))
      (node (ref "D4") (pin "2") (pinfunction "K_2") (pintype "passive"))
      (node (ref "P13") (pin "7") (pinfunction "7_7") (pintype "passive"))
      (node (ref "P13") (pin "8") (pinfunction "8_8") (pintype "passive"))
      (node (ref "R1") (pin "1") (pintype "passive"))
      (node (ref "R2") (pin "1") (pintype "passive"))
      (node (ref "R23") (pin "1") (pintype "passive"))
      (node (ref "R4") (pin "1") (pintype "passive"))
      (node (ref "R6") (pin "2") (pinfunction "2_2") (pintype "passive"))
      (node (ref "U2") (pin "100") (pinfunction "VDD_100") (pintype "power_in"))
      (node (ref "U2") (pin "11") (pinfunction "VDD_11") (pintype "power_in"))
      (node (ref "U2") (pin "28") (pinfunction "VDD_28") (pintype "power_in"))
      (node (ref "U2") (pin "46") (pinfunction "VDD_46") (pintype "power_in"))
      (node (ref "U2") (pin "75") (pinfunction "VDD_75") (pintype "power_in"))
    )
    (net (code "119") (name "unconnected-(C24-Pad1)") (class "Default")
      (node (ref "C24") (pin "1") (pinfunction "1_1") (pintype "passive"))
    )
    (net (code "120") (name "unconnected-(P10-Pad7)") (class "Default")
      (node (ref "P10") (pin "7") (pintype "passive"))
    )
    (net (code "121") (name "unconnected-(S1-NO-Pad3)") (class "Default")
      (node (ref "S1") (pin "3") (pinfunction "NO_3") (pintype "passive"))
    )
    (net (code "122") (name "unconnected-(U1-NC.-Pad1)") (class "Default")
      (node (ref "U1") (pin "1") (pinfunction "NC._1") (pintype "passive"))
    )
  )
)
